# MIXR_Processing_-_USB_Hub.net
KiCad netlist of a schematic drawn in Altium Designer
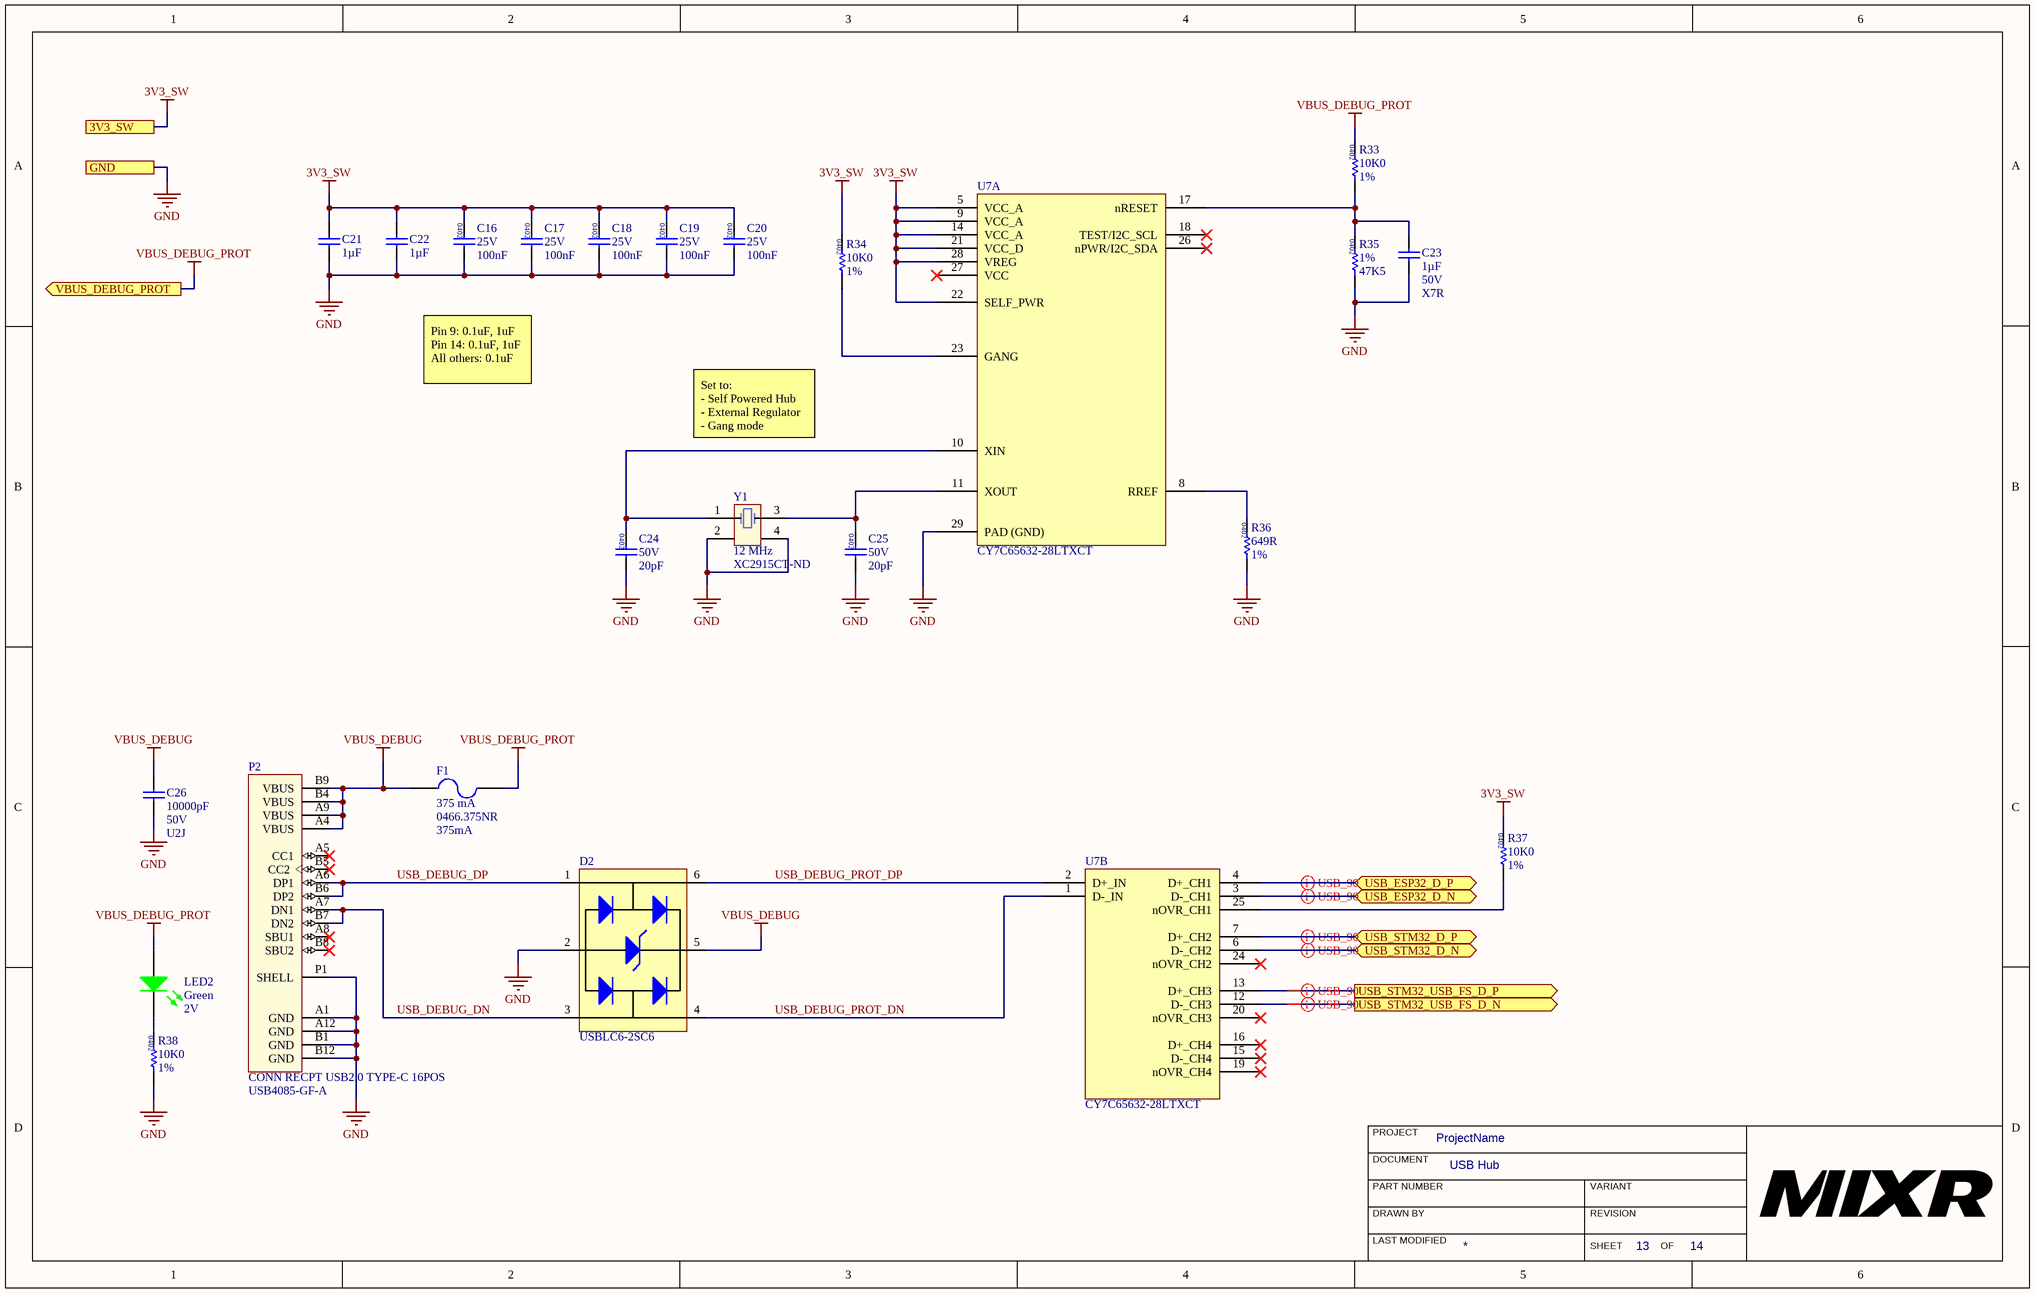
[diagram p0: MIXR Processing - USB Hub.SchDoc]

(export (version "E")
  (design (tool "Eeschema 10.0.6"))
  (components
    (comp (ref "C16")
      (value "CAP CER 0.1UF 16V X7R 0402")
      (footprint "CAP 0402")
      (description "Cap Ceramic 0.1uF 25V X7R 10% SMD 0402 125C Paper T/R")
      (fields
        (field (name "MANUFACTURER") "Murata")
        (field (name "MANUFACTURER PART NUMBER") "GRM155R71E104KE14D")
        (field (name "VOLTAGE") "25V")
        (field (name "CAPACITANCE") "100nF")
      )
      (libsource (lib "Schematic Diagrams") (part "CAP CER 0.1UF 16V X7R 0402"))
    )
    (comp (ref "C17")
      (value "CAP CER 0.1UF 16V X7R 0402")
      (footprint "CAP 0402")
      (description "Cap Ceramic 0.1uF 25V X7R 10% SMD 0402 125C Paper T/R")
      (fields
        (field (name "MANUFACTURER") "Murata")
        (field (name "MANUFACTURER PART NUMBER") "GRM155R71E104KE14D")
        (field (name "VOLTAGE") "25V")
        (field (name "CAPACITANCE") "100nF")
      )
      (libsource (lib "Schematic Diagrams") (part "CAP CER 0.1UF 16V X7R 0402"))
    )
    (comp (ref "C18")
      (value "CAP CER 0.1UF 16V X7R 0402")
      (footprint "CAP 0402")
      (description "Cap Ceramic 0.1uF 25V X7R 10% SMD 0402 125C Paper T/R")
      (fields
        (field (name "MANUFACTURER") "Murata")
        (field (name "MANUFACTURER PART NUMBER") "GRM155R71E104KE14D")
        (field (name "VOLTAGE") "25V")
        (field (name "CAPACITANCE") "100nF")
      )
      (libsource (lib "Schematic Diagrams") (part "CAP CER 0.1UF 16V X7R 0402"))
    )
    (comp (ref "C19")
      (value "CAP CER 0.1UF 16V X7R 0402")
      (footprint "CAP 0402")
      (description "Cap Ceramic 0.1uF 25V X7R 10% SMD 0402 125C Paper T/R")
      (fields
        (field (name "MANUFACTURER") "Murata")
        (field (name "MANUFACTURER PART NUMBER") "GRM155R71E104KE14D")
        (field (name "VOLTAGE") "25V")
        (field (name "CAPACITANCE") "100nF")
      )
      (libsource (lib "Schematic Diagrams") (part "CAP CER 0.1UF 16V X7R 0402"))
    )
    (comp (ref "C20")
      (value "CAP CER 0.1UF 16V X7R 0402")
      (footprint "CAP 0402")
      (description "Cap Ceramic 0.1uF 25V X7R 10% SMD 0402 125C Paper T/R")
      (fields
        (field (name "MANUFACTURER") "Murata")
        (field (name "MANUFACTURER PART NUMBER") "GRM155R71E104KE14D")
        (field (name "VOLTAGE") "25V")
        (field (name "CAPACITANCE") "100nF")
      )
      (libsource (lib "Schematic Diagrams") (part "CAP CER 0.1UF 16V X7R 0402"))
    )
    (comp (ref "C21")
      (value "CAP CER 1UF 50V 10% X7R 0603")
      (footprint "CAP, 0603")
      (description "1µF ±10% 50V Ceramic Capacitor X7R 0603 (1608 Metric)")
      (fields (field (name "TOLERANCE") "±10%") (field (name "CAPACITANCE") "1µF"))
      (libsource (lib "Schematic Diagrams") (part "CAP CER 1UF 50V 10% X7R 0603"))
    )
    (comp (ref "C22")
      (value "CAP CER 1UF 50V 10% X7R 0603")
      (footprint "CAP, 0603")
      (description "1µF ±10% 50V Ceramic Capacitor X7R 0603 (1608 Metric)")
      (fields
        (field (name "TOLERANCE") "±10%")
        (field (name "CAPACITANCE") "1µF")
        (field (name "VOLTAGE") "50V")
      )
      (libsource (lib "Schematic Diagrams") (part "CAP CER 1UF 50V 10% X7R 0603"))
    )
    (comp (ref "C23")
      (value "CAP CER 1UF 50V 10% X7R 0603")
      (footprint "CAP, 0603")
      (description "1µF ±10% 50V Ceramic Capacitor X7R 0603 (1608 Metric)")
      (fields
        (field (name "TOLERANCE") "±10%")
        (field (name "CAPACITANCE") "1µF")
        (field (name "VOLTAGE") "50V")
        (field (name "TEMPERATURE COEFFICIENT") "X7R")
      )
      (libsource (lib "Schematic Diagrams") (part "CAP CER 1UF 50V 10% X7R 0603"))
    )
    (comp (ref "C24")
      (value "CAP CER 20PF 50V C0G/NPO 0402")
      (footprint "CAP 0402")
      (description "Cap Ceramic 20pF 50V C0G 5% SMD 0402 125C Paper T/R")
      (fields
        (field (name "MANUFACTURER") "Samsung")
        (field (name "MANUFACTURER PART NUMBER") "CL05C200JB5NNNC")
        (field (name "VOLTAGE RATING") "50V")
        (field (name "CAPACITANCE") "20pF")
      )
      (libsource (lib "Schematic Diagrams") (part "CAP CER 20PF 50V C0G/NPO 0402"))
    )
    (comp (ref "C25")
      (value "CAP CER 20PF 50V C0G/NPO 0402")
      (footprint "CAP 0402")
      (description "Cap Ceramic 20pF 50V C0G 5% SMD 0402 125C Paper T/R")
      (fields
        (field (name "MANUFACTURER") "Samsung")
        (field (name "MANUFACTURER PART NUMBER") "CL05C200JB5NNNC")
        (field (name "VOLTAGE RATING") "50V")
        (field (name "CAPACITANCE") "20pF")
      )
      (libsource (lib "Schematic Diagrams") (part "CAP CER 20PF 50V C0G/NPO 0402"))
    )
    (comp (ref "C26")
      (value "CAP CER 10nF 50V 5% X7R 0603")
      (footprint "CAP, 0603")
      (description "10000pF ±5% 50V Ceramic Capacitor U2J 0603 (1608 Metric)")
      (fields
        (field (name "TOLERANCE") "±5%")
        (field (name "CAPACITANCE") "10000pF")
        (field (name "VOLTAGE") "50V")
        (field (name "TEMPERATURE COEFFICIENT") "U2J")
      )
      (libsource (lib "Schematic Diagrams") (part "CAP CER 10nF 50V 5% X7R 0603"))
    )
    (comp (ref "D2")
      (value "DIODE TVS 5.25V 17V SOT23-6")
      (footprint "SOT23-6")
      (description "17V Clamp 5A (8/20µs) Ipp Tvs Diode Surface Mount SOT-23-6")
      (fields (field (name "MANUFACTURER PART NUMBER 1") "USBLC6-2SC6"))
      (libsource (lib "Schematic Diagrams") (part "DIODE TVS 5.25V 17V SOT23-6"))
    )
    (comp (ref "F1")
      (value "375 mA")
      (footprint "FUSE LITTLEFUSE 0466 1206")
      (description "FUSE BOARD MNT 375MA 125VAC/VDC")
      (fields
        (field (name "MANUFACTURER") "Littelfuse")
        (field (name "MANUFACTURER PART NUMBER") "0466.375NR")
        (field (name "CURRENT RATING") "375mA")
      )
      (libsource (lib "Schematic Diagrams") (part "FUSE 375MA 125VDC 1206"))
    )
    (comp (ref "LED2")
      (value "LED GREEN CLEAR 2V 0603")
      (footprint "LED_0603")
      (description "Green 572nm LED Indication - Discrete 2V 0603 (1608 Metric)")
      (fields
        (field (name "MANUFACTURER") "Wurth Electronics Inc.")
        (field (name "MANUFACTURER PART NUMBER") "150060VS75000")
        (field (name "COLOR") "Green")
        (field (name "VOLTAGE - FORWARD (VF) (TYP)") "2V")
      )
      (libsource (lib "Schematic Diagrams") (part "LED GREEN CLEAR 2V 0603"))
    )
    (comp (ref "P2")
      (value "CONN RECPT USB2.0 TYPE-C 16POS")
      (footprint "CONN RECPT USB2.0 TYPE C 16-POS")
      (description "USB - C USB 2.0 Receptacle Connector 16 Position Through Hole, Right Angle")
      (fields
        (field (name "MANUFACTURER") "Global Connector Technology")
        (field (name "MANUFACTURER PART NUMBER") "USB4085-GF-A")
      )
      (libsource (lib "Schematic Diagrams") (part "CONN RECPT USB2.0 TYPE-C 16POS"))
    )
    (comp (ref "R33")
      (value "RES 10K OHM 1% 1/16W 0402")
      (footprint "RES 0402")
      (description "Surface Mount Thick Film Resistor, Rc Series, 10 Kohm, 62.5 Mw, - 1%, 50 V, 0402 [1005 Metric]")
      (fields
        (field (name "MANUFACTURER") "Yageo")
        (field (name "MANUFACTURER PART NUMBER") "RC0402FR-0710KL")
        (field (name "RESISTANCE") "10K0")
        (field (name "TOLERANCE") "1%")
      )
      (libsource (lib "Schematic Diagrams") (part "RES 10K OHM 1% 1/16W 0402"))
    )
    (comp (ref "R34")
      (value "RES 10K OHM 1% 1/16W 0402")
      (footprint "RES 0402")
      (description "Surface Mount Thick Film Resistor, Rc Series, 10 Kohm, 62.5 Mw, - 1%, 50 V, 0402 [1005 Metric]")
      (fields
        (field (name "MANUFACTURER") "Yageo")
        (field (name "MANUFACTURER PART NUMBER") "RC0402FR-0710KL")
        (field (name "RESISTANCE") "10K0")
        (field (name "TOLERANCE") "1%")
      )
      (libsource (lib "Schematic Diagrams") (part "RES 10K OHM 1% 1/16W 0402"))
    )
    (comp (ref "R35")
      (value "RES 47.5K OHM 1% 1/16W 0402")
      (footprint "RES 0402")
      (description "RES SMD 47.5K OHM 1% 1/16W 0402")
      (fields
        (field (name "MANUFACTURER") "Yageo")
        (field (name "MANUFACTURER PART NUMBER") "RC0402FR-0747K5L")
        (field (name "TOLERANCE") "1%")
        (field (name "RESISTANCE") "47K5")
      )
      (libsource (lib "Schematic Diagrams") (part "RES 47.5K OHM 1% 1/16W 0402"))
    )
    (comp (ref "R36")
      (value "RES 649 OHM 1% 1/16W 0402")
      (footprint "RES 0402")
      (description "RES SMD 649 OHM 1% 1/16W 0402")
      (fields
        (field (name "MANUFACTURER") "Stackpole Electronics")
        (field (name "MANUFACTURER PART NUMBER") "RMCF0402FT649R")
        (field (name "RESISTANCE") "649R")
        (field (name "TOLERANCE") "1%")
      )
      (libsource (lib "Schematic Diagrams") (part "RES 649 OHM 1% 1/16W 0402"))
    )
    (comp (ref "R37")
      (value "RES 10K OHM 1% 1/16W 0402")
      (footprint "RES 0402")
      (description "Surface Mount Thick Film Resistor, Rc Series, 10 Kohm, 62.5 Mw, - 1%, 50 V, 0402 [1005 Metric]")
      (fields
        (field (name "MANUFACTURER") "Yageo")
        (field (name "MANUFACTURER PART NUMBER") "RC0402FR-0710KL")
        (field (name "RESISTANCE") "10K0")
        (field (name "TOLERANCE") "1%")
      )
      (libsource (lib "Schematic Diagrams") (part "RES 10K OHM 1% 1/16W 0402"))
    )
    (comp (ref "R38")
      (value "RES 10K OHM 1% 1/16W 0402")
      (footprint "RES 0402")
      (description "Surface Mount Thick Film Resistor, Rc Series, 10 Kohm, 62.5 Mw, - 1%, 50 V, 0402 [1005 Metric]")
      (fields
        (field (name "MANUFACTURER") "Yageo")
        (field (name "MANUFACTURER PART NUMBER") "RC0402FR-0710KL")
        (field (name "RESISTANCE") "10K0")
        (field (name "TOLERANCE") "1%")
      )
      (libsource (lib "Schematic Diagrams") (part "RES 10K OHM 1% 1/16W 0402"))
    )
    (comp (ref "U7")
      (value "IC USB 2.0 HUB CONTROLLER 28QFN")
      (footprint "QFN50P500X500X80-29N")
      (description "USB Hub Controller USB 2.0 USB Interface 28-QFN (5x5)")
      (fields
        (field (name "MANUFACTURER") "Cypress")
        (field (name "MANUFACTURER PART NUMBER") "CY7C65632-28LTXCT")
      )
      (libsource (lib "Schematic Diagrams") (part "IC USB 2.0 HUB CONTROLLER 28QFN"))
    )
    (comp (ref "Y1")
      (value "12 MHz")
      (footprint "CRYSTAL ECX-32")
      (description "12MHz ±25ppm Crystal 12pF 100 Ohms 4-SMD, No Lead")
      (fields
        (field (name "MANUFACTURER") "ECS International")
        (field (name "MANUFACTURER PART NUMBER") "ECS-120-12-33-AEN-TR")
        (field (name "SUPPLIER PART NUMBER 1") "XC2915CT-ND")
      )
      (libsource (lib "Schematic Diagrams") (part "CRYSTAL 12 MHz 12PF SMD"))
    )
  )
  (nets
    (net (code "1") (name "/USB_DEBUG_DN") (class "Default")
      (node (ref "D2") (pin "3") (pinfunction "Cathode1_3") (pintype "passive"))
      (node (ref "P2") (pin "A7") (pinfunction "DN1_A7") (pintype "bidirectional"))
      (node (ref "P2") (pin "B7") (pinfunction "DN2_B7") (pintype "bidirectional"))
    )
    (net (code "2") (name "/USB_DEBUG_DP") (class "Default")
      (node (ref "D2") (pin "1") (pinfunction "Cathode3_1") (pintype "passive"))
      (node (ref "P2") (pin "A6") (pinfunction "DP1_A6") (pintype "bidirectional"))
      (node (ref "P2") (pin "B6") (pinfunction "DP2_B6") (pintype "bidirectional"))
    )
    (net (code "3") (name "/USB_DEBUG_PROT_DN") (class "Default")
      (node (ref "D2") (pin "4") (pinfunction "Cathode2_4") (pintype "passive"))
      (node (ref "U7") (pin "1") (pinfunction "D-_IN_1") (pintype "passive"))
    )
    (net (code "4") (name "/USB_DEBUG_PROT_DP") (class "Default")
      (node (ref "D2") (pin "6") (pinfunction "Cathode3_6") (pintype "passive"))
      (node (ref "U7") (pin "2") (pinfunction "D+_IN_2") (pintype "passive"))
    )
    (net (code "5") (name "/USB_ESP32_D_N") (class "Default")
      (node (ref "U7") (pin "3") (pinfunction "D-_CH1_3") (pintype "passive"))
    )
    (net (code "6") (name "/USB_ESP32_D_P") (class "Default")
      (node (ref "U7") (pin "4") (pinfunction "D+_CH1_4") (pintype "passive"))
    )
    (net (code "7") (name "/USB_STM32_D_N") (class "Default")
      (node (ref "U7") (pin "6") (pinfunction "D-_CH2_6") (pintype "passive"))
    )
    (net (code "8") (name "/USB_STM32_D_P") (class "Default")
      (node (ref "U7") (pin "7") (pinfunction "D+_CH2_7") (pintype "passive"))
    )
    (net (code "9") (name "/USB_STM32_USB_FS_D_N") (class "Default")
      (node (ref "U7") (pin "12") (pinfunction "D-_CH3_12") (pintype "passive"))
    )
    (net (code "10") (name "/USB_STM32_USB_FS_D_P") (class "Default")
      (node (ref "U7") (pin "13") (pinfunction "D+_CH3_13") (pintype "passive"))
    )
    (net (code "11") (name "3V3_SW") (class "Default")
      (node (ref "C16") (pin "1") (pinfunction "1_1") (pintype "passive"))
      (node (ref "C17") (pin "1") (pinfunction "1_1") (pintype "passive"))
      (node (ref "C18") (pin "1") (pinfunction "1_1") (pintype "passive"))
      (node (ref "C19") (pin "1") (pinfunction "1_1") (pintype "passive"))
      (node (ref "C20") (pin "1") (pinfunction "1_1") (pintype "passive"))
      (node (ref "C21") (pin "1") (pinfunction "1_1") (pintype "passive"))
      (node (ref "C22") (pin "1") (pinfunction "1_1") (pintype "passive"))
      (node (ref "R34") (pin "1") (pinfunction "1_1") (pintype "passive"))
      (node (ref "R37") (pin "1") (pinfunction "1_1") (pintype "passive"))
      (node (ref "U7") (pin "14") (pinfunction "VCC_A_14") (pintype "passive"))
      (node (ref "U7") (pin "21") (pinfunction "VCC_D_21") (pintype "passive"))
      (node (ref "U7") (pin "22") (pinfunction "SELF_PWR_22") (pintype "passive"))
      (node (ref "U7") (pin "28") (pinfunction "VREG_28") (pintype "passive"))
      (node (ref "U7") (pin "5") (pinfunction "VCC_A_5") (pintype "passive"))
      (node (ref "U7") (pin "9") (pinfunction "VCC_A_9") (pintype "passive"))
    )
    (net (code "12") (name "GND") (class "Default")
      (node (ref "C16") (pin "2") (pinfunction "2_2") (pintype "passive"))
      (node (ref "C17") (pin "2") (pinfunction "2_2") (pintype "passive"))
      (node (ref "C18") (pin "2") (pinfunction "2_2") (pintype "passive"))
      (node (ref "C19") (pin "2") (pinfunction "2_2") (pintype "passive"))
      (node (ref "C20") (pin "2") (pinfunction "2_2") (pintype "passive"))
      (node (ref "C21") (pin "2") (pinfunction "2_2") (pintype "passive"))
      (node (ref "C22") (pin "2") (pinfunction "2_2") (pintype "passive"))
      (node (ref "C23") (pin "2") (pinfunction "2_2") (pintype "passive"))
      (node (ref "C24") (pin "2") (pinfunction "2_2") (pintype "passive"))
      (node (ref "C25") (pin "2") (pinfunction "2_2") (pintype "passive"))
      (node (ref "C26") (pin "2") (pinfunction "2_2") (pintype "passive"))
      (node (ref "D2") (pin "2") (pinfunction "Cathode2_2") (pintype "passive"))
      (node (ref "P2") (pin "A1") (pinfunction "GND_A1") (pintype "power_in"))
      (node (ref "P2") (pin "A12") (pinfunction "GND_A12") (pintype "power_in"))
      (node (ref "P2") (pin "B1") (pinfunction "GND_B1") (pintype "passive"))
      (node (ref "P2") (pin "B12") (pinfunction "GND_B12") (pintype "power_in"))
      (node (ref "P2") (pin "P1") (pinfunction "SHELL_P1") (pintype "passive"))
      (node (ref "R35") (pin "2") (pinfunction "2_2") (pintype "passive"))
      (node (ref "R36") (pin "2") (pinfunction "2_2") (pintype "passive"))
      (node (ref "R38") (pin "2") (pinfunction "2_2") (pintype "passive"))
      (node (ref "U7") (pin "29") (pinfunction "PAD_(GND)_29") (pintype "passive"))
      (node (ref "Y1") (pin "2") (pinfunction "2_2") (pintype "passive"))
      (node (ref "Y1") (pin "4") (pinfunction "3_4") (pintype "passive"))
    )
    (net (code "13") (name "Net-(LED2-K)") (class "Default")
      (node (ref "LED2") (pin "2") (pinfunction "K_2") (pintype "passive"))
      (node (ref "R38") (pin "1") (pinfunction "1_1") (pintype "passive"))
    )
    (net (code "14") (name "Net-(U7A-GANG)") (class "Default")
      (node (ref "R34") (pin "2") (pinfunction "2_2") (pintype "passive"))
      (node (ref "U7") (pin "23") (pinfunction "GANG_23") (pintype "passive"))
    )
    (net (code "15") (name "Net-(U7A-RREF)") (class "Default")
      (node (ref "R36") (pin "1") (pinfunction "1_1") (pintype "passive"))
      (node (ref "U7") (pin "8") (pinfunction "RREF_8") (pintype "passive"))
    )
    (net (code "16") (name "Net-(U7A-XIN)") (class "Default")
      (node (ref "C24") (pin "1") (pinfunction "1_1") (pintype "passive"))
      (node (ref "U7") (pin "10") (pinfunction "XIN_10") (pintype "passive"))
      (node (ref "Y1") (pin "1") (pinfunction "OSC1_1") (pintype "passive"))
    )
    (net (code "17") (name "Net-(U7A-XOUT)") (class "Default")
      (node (ref "C25") (pin "1") (pinfunction "1_1") (pintype "passive"))
      (node (ref "U7") (pin "11") (pinfunction "XOUT_11") (pintype "passive"))
      (node (ref "Y1") (pin "3") (pinfunction "OSC2_3") (pintype "passive"))
    )
    (net (code "18") (name "Net-(U7A-nRESET)") (class "Default")
      (node (ref "C23") (pin "1") (pinfunction "1_1") (pintype "passive"))
      (node (ref "R33") (pin "2") (pinfunction "2_2") (pintype "passive"))
      (node (ref "R35") (pin "1") (pinfunction "1_1") (pintype "passive"))
      (node (ref "U7") (pin "17") (pinfunction "nRESET_17") (pintype "passive"))
    )
    (net (code "19") (name "Net-(U7B-nOVR_CH1)") (class "Default")
      (node (ref "R37") (pin "2") (pinfunction "2_2") (pintype "passive"))
      (node (ref "U7") (pin "25") (pinfunction "nOVR_CH1_25") (pintype "passive"))
    )
    (net (code "20") (name "VBUS_DEBUG") (class "Default")
      (node (ref "C26") (pin "1") (pinfunction "1_1") (pintype "passive"))
      (node (ref "D2") (pin "5") (pinfunction "Cathode4_5") (pintype "passive"))
      (node (ref "F1") (pin "1") (pinfunction "1_1") (pintype "passive"))
      (node (ref "P2") (pin "A4") (pinfunction "VBUS_A4") (pintype "power_in"))
      (node (ref "P2") (pin "A9") (pinfunction "VBUS_A9") (pintype "power_in"))
      (node (ref "P2") (pin "B4") (pinfunction "VBUS_B4") (pintype "power_in"))
      (node (ref "P2") (pin "B9") (pinfunction "VBUS_B9") (pintype "power_in"))
    )
    (net (code "21") (name "VBUS_DEBUG_PROT") (class "Default")
      (node (ref "F1") (pin "2") (pinfunction "2_2") (pintype "passive"))
      (node (ref "LED2") (pin "1") (pinfunction "A_1") (pintype "passive"))
      (node (ref "R33") (pin "1") (pinfunction "1_1") (pintype "passive"))
    )
    (net (code "22") (name "unconnected-(P2-CC1-PadA5)") (class "Default")
      (node (ref "P2") (pin "A5") (pinfunction "CC1_A5") (pintype "bidirectional+no_connect"))
    )
    (net (code "23") (name "unconnected-(P2-CC2-PadB5)") (class "Default")
      (node (ref "P2") (pin "B5") (pinfunction "CC2_B5") (pintype "bidirectional+no_connect"))
    )
    (net (code "24") (name "unconnected-(P2-SBU1-PadA8)") (class "Default")
      (node (ref "P2") (pin "A8") (pinfunction "SBU1_A8") (pintype "bidirectional+no_connect"))
    )
    (net (code "25") (name "unconnected-(P2-SBU2-PadB8)") (class "Default")
      (node (ref "P2") (pin "B8") (pinfunction "SBU2_B8") (pintype "bidirectional+no_connect"))
    )
    (net (code "26") (name "unconnected-(U7A-TEST{slash}I2C_SCL-Pad18)") (class "Default")
      (node (ref "U7") (pin "18") (pinfunction "TEST/I2C_SCL_18") (pintype "passive+no_connect"))
    )
    (net (code "27") (name "unconnected-(U7A-VCC-Pad27)") (class "Default")
      (node (ref "U7") (pin "27") (pinfunction "VCC_27") (pintype "passive+no_connect"))
    )
    (net (code "28") (name "unconnected-(U7A-nPWR{slash}I2C_SDA-Pad26)") (class "Default")
      (node (ref "U7") (pin "26") (pinfunction "nPWR/I2C_SDA_26") (pintype "passive+no_connect"))
    )
    (net (code "29") (name "unconnected-(U7B-D+_CH4-Pad16)") (class "Default")
      (node (ref "U7") (pin "16") (pinfunction "D+_CH4_16") (pintype "passive+no_connect"))
    )
    (net (code "30") (name "unconnected-(U7B-D-_CH4-Pad15)") (class "Default")
      (node (ref "U7") (pin "15") (pinfunction "D-_CH4_15") (pintype "passive+no_connect"))
    )
    (net (code "31") (name "unconnected-(U7B-nOVR_CH2-Pad24)") (class "Default")
      (node (ref "U7") (pin "24") (pinfunction "nOVR_CH2_24") (pintype "passive+no_connect"))
    )
    (net (code "32") (name "unconnected-(U7B-nOVR_CH3-Pad20)") (class "Default")
      (node (ref "U7") (pin "20") (pinfunction "nOVR_CH3_20") (pintype "passive+no_connect"))
    )
    (net (code "33") (name "unconnected-(U7B-nOVR_CH4-Pad19)") (class "Default")
      (node (ref "U7") (pin "19") (pinfunction "nOVR_CH4_19") (pintype "passive+no_connect"))
    )
  )
)
